# master_teststand_v1.net
KiCad netlist of a schematic drawn in EAGLE
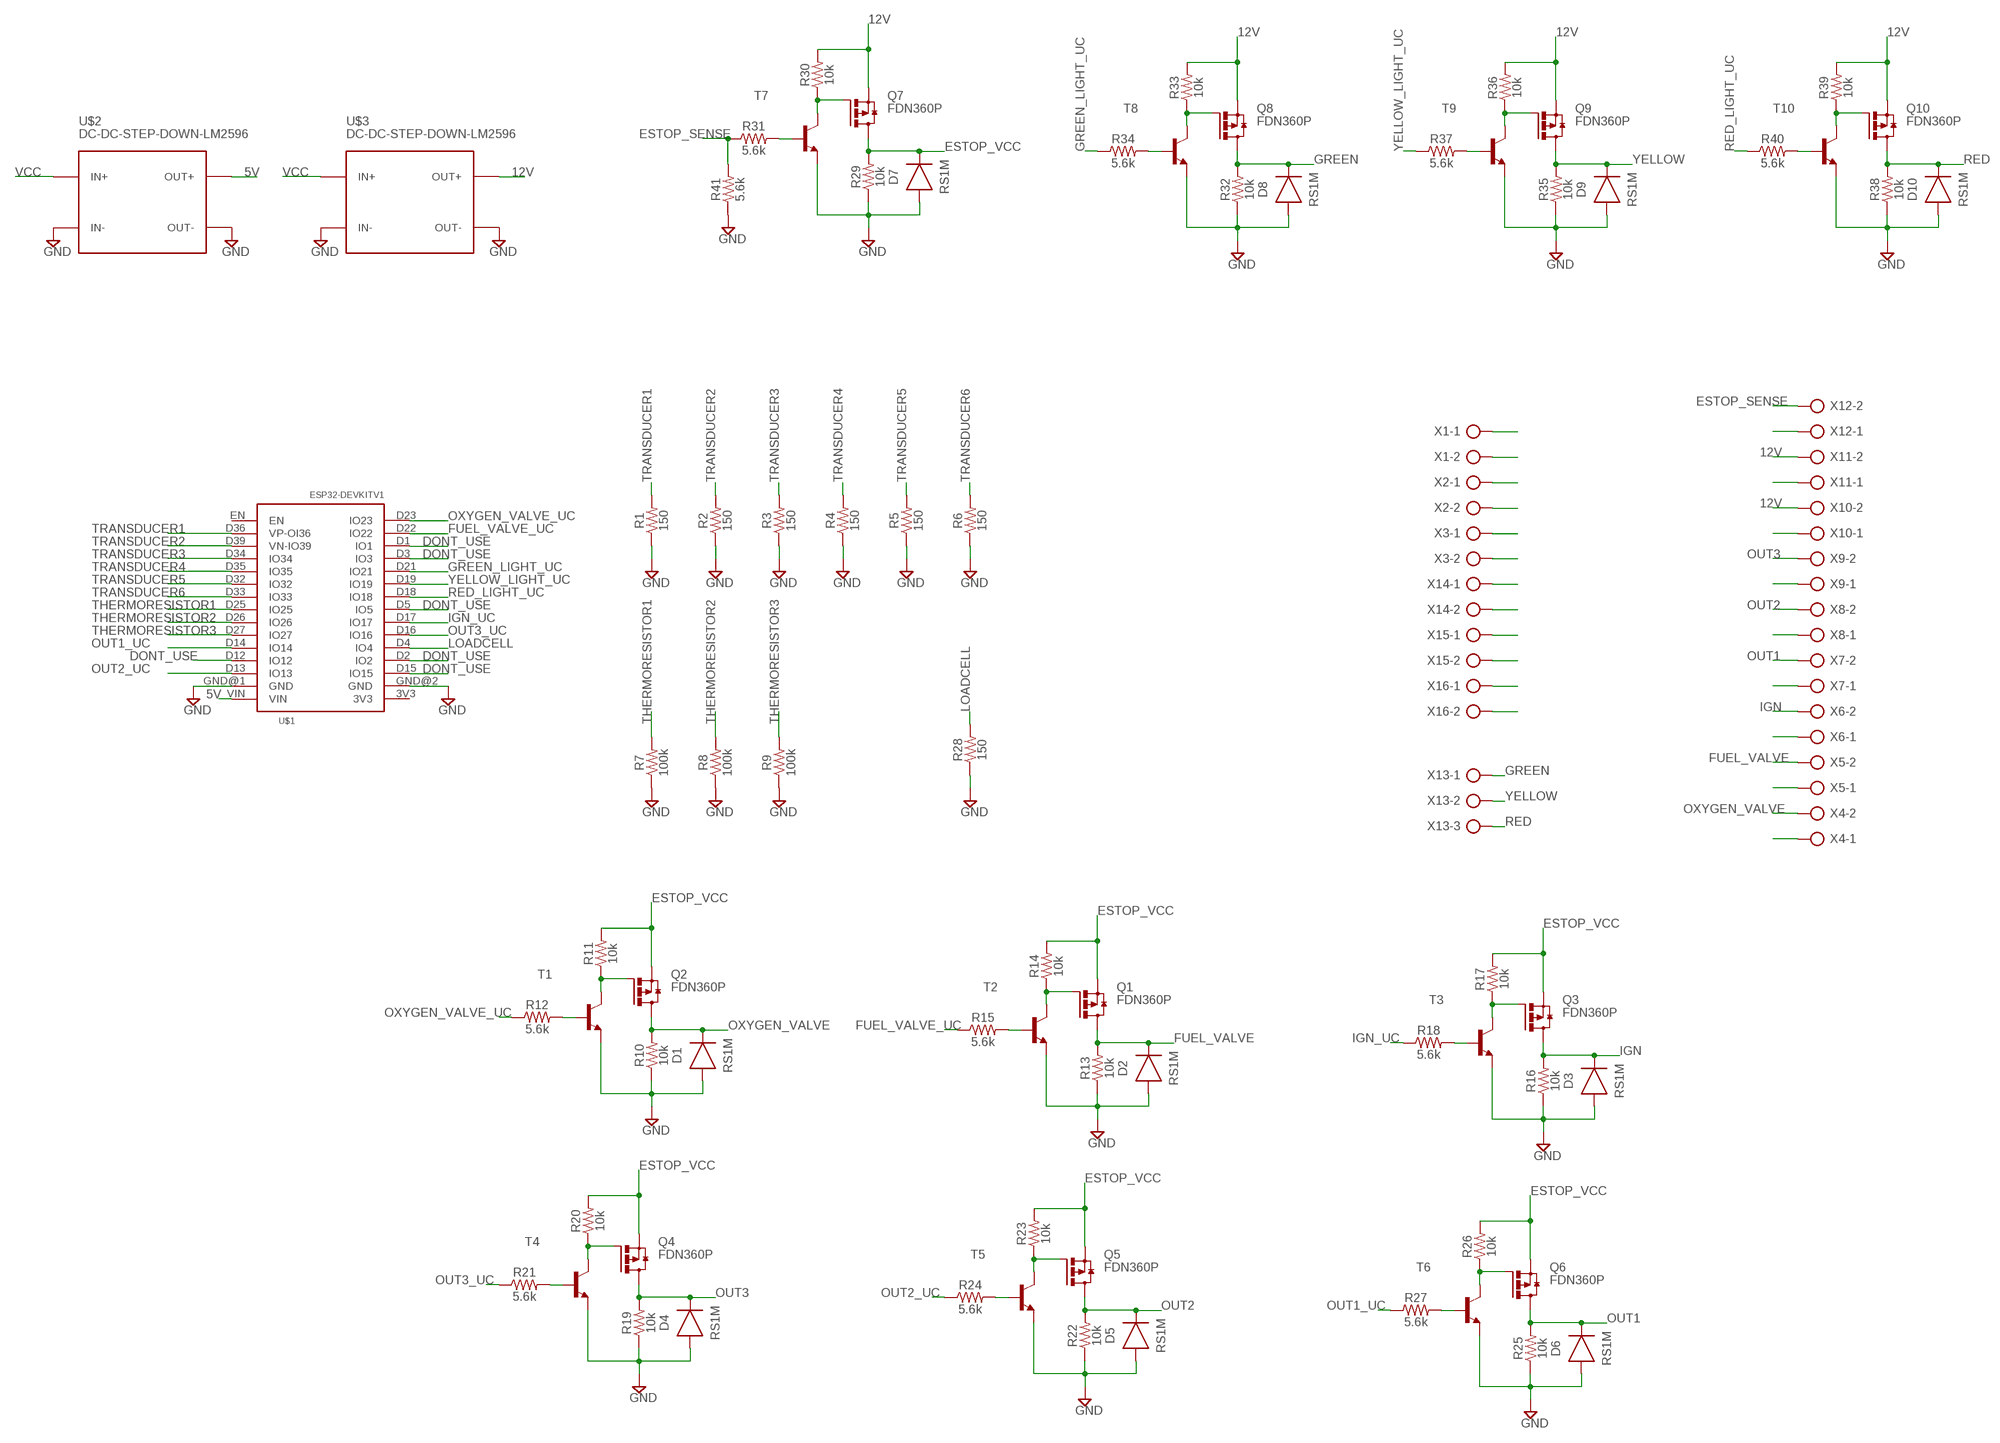
[diagram p0: schematic, sheet 1]

(export (version "E")
  (design (tool "Eeschema 10.0.6"))
  (components
    (comp (ref "D1")
      (value "RS1M")
      (footprint "eagle-import:DIOM5226X290N")
      (fields (field (name "MANUFACTURER") "ON Semiconductor "))
      (libsource (lib "eagle-import") (part "DIODE__SMARS1M"))
    )
    (comp (ref "D2")
      (value "RS1M")
      (footprint "eagle-import:DIOM5226X290N")
      (fields (field (name "MANUFACTURER") "ON Semiconductor "))
      (libsource (lib "eagle-import") (part "DIODE__SMARS1M"))
    )
    (comp (ref "D3")
      (value "RS1M")
      (footprint "eagle-import:DIOM5226X290N")
      (fields (field (name "MANUFACTURER") "ON Semiconductor "))
      (libsource (lib "eagle-import") (part "DIODE__SMARS1M"))
    )
    (comp (ref "D4")
      (value "RS1M")
      (footprint "eagle-import:DIOM5226X290N")
      (fields (field (name "MANUFACTURER") "ON Semiconductor "))
      (libsource (lib "eagle-import") (part "DIODE__SMARS1M"))
    )
    (comp (ref "D5")
      (value "RS1M")
      (footprint "eagle-import:DIOM5226X290N")
      (fields (field (name "MANUFACTURER") "ON Semiconductor "))
      (libsource (lib "eagle-import") (part "DIODE__SMARS1M"))
    )
    (comp (ref "D6")
      (value "RS1M")
      (footprint "eagle-import:DIOM5226X290N")
      (fields (field (name "MANUFACTURER") "ON Semiconductor "))
      (libsource (lib "eagle-import") (part "DIODE__SMARS1M"))
    )
    (comp (ref "D7")
      (value "RS1M")
      (footprint "eagle-import:DIOM5226X290N")
      (fields (field (name "MANUFACTURER") "ON Semiconductor "))
      (libsource (lib "eagle-import") (part "DIODE__SMARS1M"))
    )
    (comp (ref "D8")
      (value "RS1M")
      (footprint "eagle-import:DIOM5226X290N")
      (fields (field (name "MANUFACTURER") "ON Semiconductor "))
      (libsource (lib "eagle-import") (part "DIODE__SMARS1M"))
    )
    (comp (ref "D9")
      (value "RS1M")
      (footprint "eagle-import:DIOM5226X290N")
      (fields (field (name "MANUFACTURER") "ON Semiconductor "))
      (libsource (lib "eagle-import") (part "DIODE__SMARS1M"))
    )
    (comp (ref "D10")
      (value "RS1M")
      (footprint "eagle-import:DIOM5226X290N")
      (fields (field (name "MANUFACTURER") "ON Semiconductor "))
      (libsource (lib "eagle-import") (part "DIODE__SMARS1M"))
    )
    (comp (ref "Q1")
      (value "FDN360P")
      (footprint "eagle-import:SUPER-SOT3")
      (libsource (lib "eagle-import") (part "FDN360P"))
    )
    (comp (ref "Q2")
      (value "FDN360P")
      (footprint "eagle-import:SUPER-SOT3")
      (libsource (lib "eagle-import") (part "FDN360P"))
    )
    (comp (ref "Q3")
      (value "FDN360P")
      (footprint "eagle-import:SUPER-SOT3")
      (libsource (lib "eagle-import") (part "FDN360P"))
    )
    (comp (ref "Q4")
      (value "FDN360P")
      (footprint "eagle-import:SUPER-SOT3")
      (libsource (lib "eagle-import") (part "FDN360P"))
    )
    (comp (ref "Q5")
      (value "FDN360P")
      (footprint "eagle-import:SUPER-SOT3")
      (libsource (lib "eagle-import") (part "FDN360P"))
    )
    (comp (ref "Q6")
      (value "FDN360P")
      (footprint "eagle-import:SUPER-SOT3")
      (libsource (lib "eagle-import") (part "FDN360P"))
    )
    (comp (ref "Q7")
      (value "FDN360P")
      (footprint "eagle-import:SUPER-SOT3")
      (libsource (lib "eagle-import") (part "FDN360P"))
    )
    (comp (ref "Q8")
      (value "FDN360P")
      (footprint "eagle-import:SUPER-SOT3")
      (libsource (lib "eagle-import") (part "FDN360P"))
    )
    (comp (ref "Q9")
      (value "FDN360P")
      (footprint "eagle-import:SUPER-SOT3")
      (libsource (lib "eagle-import") (part "FDN360P"))
    )
    (comp (ref "Q10")
      (value "FDN360P")
      (footprint "eagle-import:SUPER-SOT3")
      (libsource (lib "eagle-import") (part "FDN360P"))
    )
    (comp (ref "R1")
      (value "150")
      (footprint "eagle-import:0603")
      (libsource (lib "eagle-import") (part "150OHM-0603-1/10W-1%"))
    )
    (comp (ref "R2")
      (value "150")
      (footprint "eagle-import:0603")
      (libsource (lib "eagle-import") (part "150OHM-0603-1/10W-1%"))
    )
    (comp (ref "R3")
      (value "150")
      (footprint "eagle-import:0603")
      (libsource (lib "eagle-import") (part "150OHM-0603-1/10W-1%"))
    )
    (comp (ref "R4")
      (value "150")
      (footprint "eagle-import:0603")
      (libsource (lib "eagle-import") (part "150OHM-0603-1/10W-1%"))
    )
    (comp (ref "R5")
      (value "150")
      (footprint "eagle-import:0603")
      (libsource (lib "eagle-import") (part "150OHM-0603-1/10W-1%"))
    )
    (comp (ref "R6")
      (value "150")
      (footprint "eagle-import:0603")
      (libsource (lib "eagle-import") (part "150OHM-0603-1/10W-1%"))
    )
    (comp (ref "R7")
      (value "100k")
      (footprint "eagle-import:0603")
      (libsource (lib "eagle-import") (part "100KOHM-0603-1/10W-1%"))
    )
    (comp (ref "R8")
      (value "100k")
      (footprint "eagle-import:0603")
      (libsource (lib "eagle-import") (part "100KOHM-0603-1/10W-1%"))
    )
    (comp (ref "R9")
      (value "100k")
      (footprint "eagle-import:0603")
      (libsource (lib "eagle-import") (part "100KOHM-0603-1/10W-1%"))
    )
    (comp (ref "R10")
      (value "10k")
      (footprint "eagle-import:0603")
      (libsource (lib "eagle-import") (part "10KOHM-0603-1/10W-1%"))
    )
    (comp (ref "R11")
      (value "10k")
      (footprint "eagle-import:0603")
      (libsource (lib "eagle-import") (part "10KOHM-0603-1/10W-1%"))
    )
    (comp (ref "R12")
      (value "5.6k")
      (footprint "eagle-import:0603")
      (libsource (lib "eagle-import") (part "5.6KOHM-0603-1/10W-1%"))
    )
    (comp (ref "R13")
      (value "10k")
      (footprint "eagle-import:0603")
      (libsource (lib "eagle-import") (part "10KOHM-0603-1/10W-1%"))
    )
    (comp (ref "R14")
      (value "10k")
      (footprint "eagle-import:0603")
      (libsource (lib "eagle-import") (part "10KOHM-0603-1/10W-1%"))
    )
    (comp (ref "R15")
      (value "5.6k")
      (footprint "eagle-import:0603")
      (libsource (lib "eagle-import") (part "5.6KOHM-0603-1/10W-1%"))
    )
    (comp (ref "R16")
      (value "10k")
      (footprint "eagle-import:0603")
      (libsource (lib "eagle-import") (part "10KOHM-0603-1/10W-1%"))
    )
    (comp (ref "R17")
      (value "10k")
      (footprint "eagle-import:0603")
      (libsource (lib "eagle-import") (part "10KOHM-0603-1/10W-1%"))
    )
    (comp (ref "R18")
      (value "5.6k")
      (footprint "eagle-import:0603")
      (libsource (lib "eagle-import") (part "5.6KOHM-0603-1/10W-1%"))
    )
    (comp (ref "R19")
      (value "10k")
      (footprint "eagle-import:0603")
      (libsource (lib "eagle-import") (part "10KOHM-0603-1/10W-1%"))
    )
    (comp (ref "R20")
      (value "10k")
      (footprint "eagle-import:0603")
      (libsource (lib "eagle-import") (part "10KOHM-0603-1/10W-1%"))
    )
    (comp (ref "R21")
      (value "5.6k")
      (footprint "eagle-import:0603")
      (libsource (lib "eagle-import") (part "5.6KOHM-0603-1/10W-1%"))
    )
    (comp (ref "R22")
      (value "10k")
      (footprint "eagle-import:0603")
      (libsource (lib "eagle-import") (part "10KOHM-0603-1/10W-1%"))
    )
    (comp (ref "R23")
      (value "10k")
      (footprint "eagle-import:0603")
      (libsource (lib "eagle-import") (part "10KOHM-0603-1/10W-1%"))
    )
    (comp (ref "R24")
      (value "5.6k")
      (footprint "eagle-import:0603")
      (libsource (lib "eagle-import") (part "5.6KOHM-0603-1/10W-1%"))
    )
    (comp (ref "R25")
      (value "10k")
      (footprint "eagle-import:0603")
      (libsource (lib "eagle-import") (part "10KOHM-0603-1/10W-1%"))
    )
    (comp (ref "R26")
      (value "10k")
      (footprint "eagle-import:0603")
      (libsource (lib "eagle-import") (part "10KOHM-0603-1/10W-1%"))
    )
    (comp (ref "R27")
      (value "5.6k")
      (footprint "eagle-import:0603")
      (libsource (lib "eagle-import") (part "5.6KOHM-0603-1/10W-1%"))
    )
    (comp (ref "R28")
      (value "150")
      (footprint "eagle-import:0603")
      (libsource (lib "eagle-import") (part "150OHM-0603-1/10W-1%"))
    )
    (comp (ref "R29")
      (value "10k")
      (footprint "eagle-import:0603")
      (libsource (lib "eagle-import") (part "10KOHM-0603-1/10W-1%"))
    )
    (comp (ref "R30")
      (value "10k")
      (footprint "eagle-import:0603")
      (libsource (lib "eagle-import") (part "10KOHM-0603-1/10W-1%"))
    )
    (comp (ref "R31")
      (value "5.6k")
      (footprint "eagle-import:0603")
      (libsource (lib "eagle-import") (part "5.6KOHM-0603-1/10W-1%"))
    )
    (comp (ref "R32")
      (value "10k")
      (footprint "eagle-import:0603")
      (libsource (lib "eagle-import") (part "10KOHM-0603-1/10W-1%"))
    )
    (comp (ref "R33")
      (value "10k")
      (footprint "eagle-import:0603")
      (libsource (lib "eagle-import") (part "10KOHM-0603-1/10W-1%"))
    )
    (comp (ref "R34")
      (value "5.6k")
      (footprint "eagle-import:0603")
      (libsource (lib "eagle-import") (part "5.6KOHM-0603-1/10W-1%"))
    )
    (comp (ref "R35")
      (value "10k")
      (footprint "eagle-import:0603")
      (libsource (lib "eagle-import") (part "10KOHM-0603-1/10W-1%"))
    )
    (comp (ref "R36")
      (value "10k")
      (footprint "eagle-import:0603")
      (libsource (lib "eagle-import") (part "10KOHM-0603-1/10W-1%"))
    )
    (comp (ref "R37")
      (value "5.6k")
      (footprint "eagle-import:0603")
      (libsource (lib "eagle-import") (part "5.6KOHM-0603-1/10W-1%"))
    )
    (comp (ref "R38")
      (value "10k")
      (footprint "eagle-import:0603")
      (libsource (lib "eagle-import") (part "10KOHM-0603-1/10W-1%"))
    )
    (comp (ref "R39")
      (value "10k")
      (footprint "eagle-import:0603")
      (libsource (lib "eagle-import") (part "10KOHM-0603-1/10W-1%"))
    )
    (comp (ref "R40")
      (value "5.6k")
      (footprint "eagle-import:0603")
      (libsource (lib "eagle-import") (part "5.6KOHM-0603-1/10W-1%"))
    )
    (comp (ref "R41")
      (value "5.6k")
      (footprint "eagle-import:0603")
      (libsource (lib "eagle-import") (part "5.6KOHM-0603-1/10W-1%"))
    )
    (comp (ref "T1")
      (value "MMBT2222ALT1-NPN-SOT23-BEC")
      (footprint "eagle-import:SOT23-BEC")
      (libsource (lib "eagle-import") (part "-NPN-SOT23-BECMMBT2222ALT1"))
    )
    (comp (ref "T2")
      (value "MMBT2222ALT1-NPN-SOT23-BEC")
      (footprint "eagle-import:SOT23-BEC")
      (libsource (lib "eagle-import") (part "-NPN-SOT23-BECMMBT2222ALT1"))
    )
    (comp (ref "T3")
      (value "MMBT2222ALT1-NPN-SOT23-BEC")
      (footprint "eagle-import:SOT23-BEC")
      (libsource (lib "eagle-import") (part "-NPN-SOT23-BECMMBT2222ALT1"))
    )
    (comp (ref "T4")
      (value "MMBT2222ALT1-NPN-SOT23-BEC")
      (footprint "eagle-import:SOT23-BEC")
      (libsource (lib "eagle-import") (part "-NPN-SOT23-BECMMBT2222ALT1"))
    )
    (comp (ref "T5")
      (value "MMBT2222ALT1-NPN-SOT23-BEC")
      (footprint "eagle-import:SOT23-BEC")
      (libsource (lib "eagle-import") (part "-NPN-SOT23-BECMMBT2222ALT1"))
    )
    (comp (ref "T6")
      (value "MMBT2222ALT1-NPN-SOT23-BEC")
      (footprint "eagle-import:SOT23-BEC")
      (libsource (lib "eagle-import") (part "-NPN-SOT23-BECMMBT2222ALT1"))
    )
    (comp (ref "T7")
      (value "MMBT2222ALT1-NPN-SOT23-BEC")
      (footprint "eagle-import:SOT23-BEC")
      (libsource (lib "eagle-import") (part "-NPN-SOT23-BECMMBT2222ALT1"))
    )
    (comp (ref "T8")
      (value "MMBT2222ALT1-NPN-SOT23-BEC")
      (footprint "eagle-import:SOT23-BEC")
      (libsource (lib "eagle-import") (part "-NPN-SOT23-BECMMBT2222ALT1"))
    )
    (comp (ref "T9")
      (value "MMBT2222ALT1-NPN-SOT23-BEC")
      (footprint "eagle-import:SOT23-BEC")
      (libsource (lib "eagle-import") (part "-NPN-SOT23-BECMMBT2222ALT1"))
    )
    (comp (ref "T10")
      (value "MMBT2222ALT1-NPN-SOT23-BEC")
      (footprint "eagle-import:SOT23-BEC")
      (libsource (lib "eagle-import") (part "-NPN-SOT23-BECMMBT2222ALT1"))
    )
    (comp (ref "U$1")
      (value "ESP32DEVKITV1")
      (footprint "eagle-import:ESP32-DEVKITV1")
      (libsource (lib "eagle-import") (part "ESP32DEVKITV1"))
    )
    (comp (ref "U$2")
      (value "DC-DC-STEP-DOWN-LM2596")
      (footprint "eagle-import:DC-DC-STEP-DOWN-LM2596")
      (libsource (lib "eagle-import") (part "DC-DC-STEP-DOWN-LM2596"))
    )
    (comp (ref "U$3")
      (value "DC-DC-STEP-DOWN-LM2596")
      (footprint "eagle-import:DC-DC-STEP-DOWN-LM2596")
      (libsource (lib "eagle-import") (part "DC-DC-STEP-DOWN-LM2596"))
    )
    (comp (ref "X1")
      (value "AK300/2")
      (footprint "eagle-import:AK300_2")
      (libsource (lib "eagle-import") (part "AK300/2"))
    )
    (comp (ref "X2")
      (value "AK300/2")
      (footprint "eagle-import:AK300_2")
      (libsource (lib "eagle-import") (part "AK300/2"))
    )
    (comp (ref "X3")
      (value "AK300/2")
      (footprint "eagle-import:AK300_2")
      (libsource (lib "eagle-import") (part "AK300/2"))
    )
    (comp (ref "X4")
      (value "AK300/2")
      (footprint "eagle-import:AK300_2")
      (libsource (lib "eagle-import") (part "AK300/2"))
    )
    (comp (ref "X5")
      (value "AK300/2")
      (footprint "eagle-import:AK300_2")
      (libsource (lib "eagle-import") (part "AK300/2"))
    )
    (comp (ref "X6")
      (value "AK300/2")
      (footprint "eagle-import:AK300_2")
      (libsource (lib "eagle-import") (part "AK300/2"))
    )
    (comp (ref "X7")
      (value "AK300/2")
      (footprint "eagle-import:AK300_2")
      (libsource (lib "eagle-import") (part "AK300/2"))
    )
    (comp (ref "X8")
      (value "AK300/2")
      (footprint "eagle-import:AK300_2")
      (libsource (lib "eagle-import") (part "AK300/2"))
    )
    (comp (ref "X9")
      (value "AK300/2")
      (footprint "eagle-import:AK300_2")
      (libsource (lib "eagle-import") (part "AK300/2"))
    )
    (comp (ref "X10")
      (value "AK300/2")
      (footprint "eagle-import:AK300_2")
      (libsource (lib "eagle-import") (part "AK300/2"))
    )
    (comp (ref "X11")
      (value "AK300/2")
      (footprint "eagle-import:AK300_2")
      (libsource (lib "eagle-import") (part "AK300/2"))
    )
    (comp (ref "X12")
      (value "AK300/2")
      (footprint "eagle-import:AK300_2")
      (libsource (lib "eagle-import") (part "AK300/2"))
    )
    (comp (ref "X13")
      (value "AK300/3")
      (footprint "eagle-import:AK300_3")
      (libsource (lib "eagle-import") (part "AK300/3"))
    )
    (comp (ref "X14")
      (value "AK300/2")
      (footprint "eagle-import:AK300_2")
      (libsource (lib "eagle-import") (part "AK300/2"))
    )
    (comp (ref "X15")
      (value "AK300/2")
      (footprint "eagle-import:AK300_2")
      (libsource (lib "eagle-import") (part "AK300/2"))
    )
    (comp (ref "X16")
      (value "AK300/2")
      (footprint "eagle-import:AK300_2")
      (libsource (lib "eagle-import") (part "AK300/2"))
    )
  )
  (nets
    (net (code "1") (name "/5V") (class "Default")
      (node (ref "U$1") (pin "VIN") (pinfunction "VIN_VIN") (pintype "bidirectional"))
      (node (ref "U$2") (pin "OUT+") (pinfunction "OUT+_OUT+") (pintype "bidirectional"))
    )
    (net (code "2") (name "/12V") (class "Default")
      (node (ref "Q10") (pin "2") (pinfunction "S_2") (pintype "passive"))
      (node (ref "Q7") (pin "2") (pinfunction "S_2") (pintype "passive"))
      (node (ref "Q8") (pin "2") (pinfunction "S_2") (pintype "passive"))
      (node (ref "Q9") (pin "2") (pinfunction "S_2") (pintype "passive"))
      (node (ref "R30") (pin "2") (pinfunction "2_2") (pintype "passive"))
      (node (ref "R33") (pin "2") (pinfunction "2_2") (pintype "passive"))
      (node (ref "R36") (pin "2") (pinfunction "2_2") (pintype "passive"))
      (node (ref "R39") (pin "2") (pinfunction "2_2") (pintype "passive"))
      (node (ref "U$3") (pin "OUT+") (pinfunction "OUT+_OUT+") (pintype "bidirectional"))
      (node (ref "X10") (pin "2") (pinfunction "KL_2") (pintype "passive"))
      (node (ref "X11") (pin "2") (pinfunction "KL_2") (pintype "passive"))
    )
    (net (code "3") (name "/DONT_USE") (class "Default")
      (node (ref "U$1") (pin "D1") (pinfunction "IO1_D1") (pintype "bidirectional"))
      (node (ref "U$1") (pin "D12") (pinfunction "IO12_D12") (pintype "bidirectional"))
      (node (ref "U$1") (pin "D15") (pinfunction "IO15_D15") (pintype "bidirectional"))
      (node (ref "U$1") (pin "D2") (pinfunction "IO2_D2") (pintype "bidirectional"))
      (node (ref "U$1") (pin "D3") (pinfunction "IO3_D3") (pintype "bidirectional"))
      (node (ref "U$1") (pin "D5") (pinfunction "IO5_D5") (pintype "bidirectional"))
    )
    (net (code "4") (name "/ESTOP_SENSE") (class "Default")
      (node (ref "R31") (pin "1") (pinfunction "1_1") (pintype "passive"))
      (node (ref "R41") (pin "2") (pinfunction "2_2") (pintype "passive"))
      (node (ref "X12") (pin "2") (pinfunction "KL_2") (pintype "passive"))
    )
    (net (code "5") (name "/ESTOP_VCC") (class "Default")
      (node (ref "D7") (pin "1") (pinfunction "C_1") (pintype "passive"))
      (node (ref "Q1") (pin "2") (pinfunction "S_2") (pintype "passive"))
      (node (ref "Q2") (pin "2") (pinfunction "S_2") (pintype "passive"))
      (node (ref "Q3") (pin "2") (pinfunction "S_2") (pintype "passive"))
      (node (ref "Q4") (pin "2") (pinfunction "S_2") (pintype "passive"))
      (node (ref "Q5") (pin "2") (pinfunction "S_2") (pintype "passive"))
      (node (ref "Q6") (pin "2") (pinfunction "S_2") (pintype "passive"))
      (node (ref "Q7") (pin "3") (pinfunction "D_3") (pintype "passive"))
      (node (ref "R11") (pin "2") (pinfunction "2_2") (pintype "passive"))
      (node (ref "R14") (pin "2") (pinfunction "2_2") (pintype "passive"))
      (node (ref "R17") (pin "2") (pinfunction "2_2") (pintype "passive"))
      (node (ref "R20") (pin "2") (pinfunction "2_2") (pintype "passive"))
      (node (ref "R23") (pin "2") (pinfunction "2_2") (pintype "passive"))
      (node (ref "R26") (pin "2") (pinfunction "2_2") (pintype "passive"))
      (node (ref "R29") (pin "2") (pinfunction "2_2") (pintype "passive"))
    )
    (net (code "6") (name "/FUEL_VALVE") (class "Default")
      (node (ref "D2") (pin "1") (pinfunction "C_1") (pintype "passive"))
      (node (ref "Q1") (pin "3") (pinfunction "D_3") (pintype "passive"))
      (node (ref "R13") (pin "2") (pinfunction "2_2") (pintype "passive"))
      (node (ref "X5") (pin "2") (pinfunction "KL_2") (pintype "passive"))
    )
    (net (code "7") (name "/FUEL_VALVE_UC") (class "Default")
      (node (ref "R15") (pin "1") (pinfunction "1_1") (pintype "passive"))
      (node (ref "U$1") (pin "D22") (pinfunction "IO22_D22") (pintype "bidirectional"))
    )
    (net (code "8") (name "/GREEN") (class "Default")
      (node (ref "D8") (pin "1") (pinfunction "C_1") (pintype "passive"))
      (node (ref "Q8") (pin "3") (pinfunction "D_3") (pintype "passive"))
      (node (ref "R32") (pin "2") (pinfunction "2_2") (pintype "passive"))
      (node (ref "X13") (pin "1") (pinfunction "KL_1") (pintype "passive"))
    )
    (net (code "9") (name "/GREEN_LIGHT_UC") (class "Default")
      (node (ref "R34") (pin "1") (pinfunction "1_1") (pintype "passive"))
      (node (ref "U$1") (pin "D21") (pinfunction "IO21_D21") (pintype "bidirectional"))
    )
    (net (code "10") (name "/IGN") (class "Default")
      (node (ref "D3") (pin "1") (pinfunction "C_1") (pintype "passive"))
      (node (ref "Q3") (pin "3") (pinfunction "D_3") (pintype "passive"))
      (node (ref "R16") (pin "2") (pinfunction "2_2") (pintype "passive"))
      (node (ref "X6") (pin "2") (pinfunction "KL_2") (pintype "passive"))
    )
    (net (code "11") (name "/IGN_UC") (class "Default")
      (node (ref "R18") (pin "1") (pinfunction "1_1") (pintype "passive"))
      (node (ref "U$1") (pin "D17") (pinfunction "IO17_D17") (pintype "bidirectional"))
    )
    (net (code "12") (name "/LOADCELL") (class "Default")
      (node (ref "R28") (pin "2") (pinfunction "2_2") (pintype "passive"))
      (node (ref "U$1") (pin "D4") (pinfunction "IO4_D4") (pintype "bidirectional"))
    )
    (net (code "13") (name "/OUT1") (class "Default")
      (node (ref "D6") (pin "1") (pinfunction "C_1") (pintype "passive"))
      (node (ref "Q6") (pin "3") (pinfunction "D_3") (pintype "passive"))
      (node (ref "R25") (pin "2") (pinfunction "2_2") (pintype "passive"))
      (node (ref "X7") (pin "2") (pinfunction "KL_2") (pintype "passive"))
    )
    (net (code "14") (name "/OUT1_UC") (class "Default")
      (node (ref "R27") (pin "1") (pinfunction "1_1") (pintype "passive"))
      (node (ref "U$1") (pin "D14") (pinfunction "IO14_D14") (pintype "bidirectional"))
    )
    (net (code "15") (name "/OUT2") (class "Default")
      (node (ref "D5") (pin "1") (pinfunction "C_1") (pintype "passive"))
      (node (ref "Q5") (pin "3") (pinfunction "D_3") (pintype "passive"))
      (node (ref "R22") (pin "2") (pinfunction "2_2") (pintype "passive"))
      (node (ref "X8") (pin "1") (pinfunction "KL_1") (pintype "passive"))
      (node (ref "X8") (pin "2") (pinfunction "KL_2") (pintype "passive"))
    )
    (net (code "16") (name "/OUT2_UC") (class "Default")
      (node (ref "R24") (pin "1") (pinfunction "1_1") (pintype "passive"))
      (node (ref "U$1") (pin "D13") (pinfunction "IO13_D13") (pintype "bidirectional"))
    )
    (net (code "17") (name "/OUT3") (class "Default")
      (node (ref "D4") (pin "1") (pinfunction "C_1") (pintype "passive"))
      (node (ref "Q4") (pin "3") (pinfunction "D_3") (pintype "passive"))
      (node (ref "R19") (pin "2") (pinfunction "2_2") (pintype "passive"))
      (node (ref "X9") (pin "2") (pinfunction "KL_2") (pintype "passive"))
    )
    (net (code "18") (name "/OUT3_UC") (class "Default")
      (node (ref "R21") (pin "1") (pinfunction "1_1") (pintype "passive"))
      (node (ref "U$1") (pin "D16") (pinfunction "IO16_D16") (pintype "bidirectional"))
    )
    (net (code "19") (name "/OXYGEN_VALVE") (class "Default")
      (node (ref "D1") (pin "1") (pinfunction "C_1") (pintype "passive"))
      (node (ref "Q2") (pin "3") (pinfunction "D_3") (pintype "passive"))
      (node (ref "R10") (pin "2") (pinfunction "2_2") (pintype "passive"))
      (node (ref "X4") (pin "2") (pinfunction "KL_2") (pintype "passive"))
    )
    (net (code "20") (name "/OXYGEN_VALVE_UC") (class "Default")
      (node (ref "R12") (pin "1") (pinfunction "1_1") (pintype "passive"))
      (node (ref "U$1") (pin "D23") (pinfunction "IO23_D23") (pintype "bidirectional"))
    )
    (net (code "21") (name "/RED") (class "Default")
      (node (ref "D10") (pin "1") (pinfunction "C_1") (pintype "passive"))
      (node (ref "Q10") (pin "3") (pinfunction "D_3") (pintype "passive"))
      (node (ref "R38") (pin "2") (pinfunction "2_2") (pintype "passive"))
      (node (ref "X13") (pin "3") (pinfunction "KL_3") (pintype "passive"))
    )
    (net (code "22") (name "/RED_LIGHT_UC") (class "Default")
      (node (ref "R40") (pin "1") (pinfunction "1_1") (pintype "passive"))
      (node (ref "U$1") (pin "D18") (pinfunction "IO18_D18") (pintype "bidirectional"))
    )
    (net (code "23") (name "/THERMORESISTOR1") (class "Default")
      (node (ref "R7") (pin "2") (pinfunction "2_2") (pintype "passive"))
      (node (ref "U$1") (pin "D25") (pinfunction "IO25_D25") (pintype "bidirectional"))
    )
    (net (code "24") (name "/THERMORESISTOR2") (class "Default")
      (node (ref "R8") (pin "2") (pinfunction "2_2") (pintype "passive"))
      (node (ref "U$1") (pin "D26") (pinfunction "IO26_D26") (pintype "bidirectional"))
    )
    (net (code "25") (name "/THERMORESISTOR3") (class "Default")
      (node (ref "R9") (pin "2") (pinfunction "2_2") (pintype "passive"))
      (node (ref "U$1") (pin "D27") (pinfunction "IO27_D27") (pintype "bidirectional"))
    )
    (net (code "26") (name "/TRANSDUCER1") (class "Default")
      (node (ref "R1") (pin "2") (pinfunction "2_2") (pintype "passive"))
      (node (ref "U$1") (pin "D36") (pinfunction "VP-OI36_D36") (pintype "bidirectional"))
    )
    (net (code "27") (name "/TRANSDUCER2") (class "Default")
      (node (ref "R2") (pin "2") (pinfunction "2_2") (pintype "passive"))
      (node (ref "U$1") (pin "D39") (pinfunction "VN-IO39_D39") (pintype "bidirectional"))
    )
    (net (code "28") (name "/TRANSDUCER3") (class "Default")
      (node (ref "R3") (pin "2") (pinfunction "2_2") (pintype "passive"))
      (node (ref "U$1") (pin "D34") (pinfunction "IO34_D34") (pintype "bidirectional"))
    )
    (net (code "29") (name "/TRANSDUCER4") (class "Default")
      (node (ref "R4") (pin "2") (pinfunction "2_2") (pintype "passive"))
      (node (ref "U$1") (pin "D35") (pinfunction "IO35_D35") (pintype "bidirectional"))
    )
    (net (code "30") (name "/TRANSDUCER5") (class "Default")
      (node (ref "R5") (pin "2") (pinfunction "2_2") (pintype "passive"))
      (node (ref "U$1") (pin "D32") (pinfunction "IO32_D32") (pintype "bidirectional"))
    )
    (net (code "31") (name "/TRANSDUCER6") (class "Default")
      (node (ref "R6") (pin "2") (pinfunction "2_2") (pintype "passive"))
      (node (ref "U$1") (pin "D33") (pinfunction "IO33_D33") (pintype "bidirectional"))
    )
    (net (code "32") (name "/VCC") (class "Default")
      (node (ref "U$2") (pin "IN+") (pinfunction "IN+_IN+") (pintype "bidirectional"))
      (node (ref "U$3") (pin "IN+") (pinfunction "IN+_IN+") (pintype "bidirectional"))
    )
    (net (code "33") (name "/YELLOW") (class "Default")
      (node (ref "D9") (pin "1") (pinfunction "C_1") (pintype "passive"))
      (node (ref "Q9") (pin "3") (pinfunction "D_3") (pintype "passive"))
      (node (ref "R35") (pin "2") (pinfunction "2_2") (pintype "passive"))
      (node (ref "X13") (pin "2") (pinfunction "KL_2") (pintype "passive"))
    )
    (net (code "34") (name "/YELLOW_LIGHT_UC") (class "Default")
      (node (ref "R37") (pin "1") (pinfunction "1_1") (pintype "passive"))
      (node (ref "U$1") (pin "D19") (pinfunction "IO19_D19") (pintype "bidirectional"))
    )
    (net (code "35") (name "GND") (class "Default")
      (node (ref "D1") (pin "2") (pinfunction "A_2") (pintype "passive"))
      (node (ref "D10") (pin "2") (pinfunction "A_2") (pintype "passive"))
      (node (ref "D2") (pin "2") (pinfunction "A_2") (pintype "passive"))
      (node (ref "D3") (pin "2") (pinfunction "A_2") (pintype "passive"))
      (node (ref "D4") (pin "2") (pinfunction "A_2") (pintype "passive"))
      (node (ref "D5") (pin "2") (pinfunction "A_2") (pintype "passive"))
      (node (ref "D6") (pin "2") (pinfunction "A_2") (pintype "passive"))
      (node (ref "D7") (pin "2") (pinfunction "A_2") (pintype "passive"))
      (node (ref "D8") (pin "2") (pinfunction "A_2") (pintype "passive"))
      (node (ref "D9") (pin "2") (pinfunction "A_2") (pintype "passive"))
      (node (ref "R1") (pin "1") (pinfunction "1_1") (pintype "passive"))
      (node (ref "R10") (pin "1") (pinfunction "1_1") (pintype "passive"))
      (node (ref "R13") (pin "1") (pinfunction "1_1") (pintype "passive"))
      (node (ref "R16") (pin "1") (pinfunction "1_1") (pintype "passive"))
      (node (ref "R19") (pin "1") (pinfunction "1_1") (pintype "passive"))
      (node (ref "R2") (pin "1") (pinfunction "1_1") (pintype "passive"))
      (node (ref "R22") (pin "1") (pinfunction "1_1") (pintype "passive"))
      (node (ref "R25") (pin "1") (pinfunction "1_1") (pintype "passive"))
      (node (ref "R28") (pin "1") (pinfunction "1_1") (pintype "passive"))
      (node (ref "R29") (pin "1") (pinfunction "1_1") (pintype "passive"))
      (node (ref "R3") (pin "1") (pinfunction "1_1") (pintype "passive"))
      (node (ref "R32") (pin "1") (pinfunction "1_1") (pintype "passive"))
      (node (ref "R35") (pin "1") (pinfunction "1_1") (pintype "passive"))
      (node (ref "R38") (pin "1") (pinfunction "1_1") (pintype "passive"))
      (node (ref "R4") (pin "1") (pinfunction "1_1") (pintype "passive"))
      (node (ref "R41") (pin "1") (pinfunction "1_1") (pintype "passive"))
      (node (ref "R5") (pin "1") (pinfunction "1_1") (pintype "passive"))
      (node (ref "R6") (pin "1") (pinfunction "1_1") (pintype "passive"))
      (node (ref "R7") (pin "1") (pinfunction "1_1") (pintype "passive"))
      (node (ref "R8") (pin "1") (pinfunction "1_1") (pintype "passive"))
      (node (ref "R9") (pin "1") (pinfunction "1_1") (pintype "passive"))
      (node (ref "T1") (pin "E") (pinfunction "E_E") (pintype "passive"))
      (node (ref "T10") (pin "E") (pinfunction "E_E") (pintype "passive"))
      (node (ref "T2") (pin "E") (pinfunction "E_E") (pintype "passive"))
      (node (ref "T3") (pin "E") (pinfunction "E_E") (pintype "passive"))
      (node (ref "T4") (pin "E") (pinfunction "E_E") (pintype "passive"))
      (node (ref "T5") (pin "E") (pinfunction "E_E") (pintype "passive"))
      (node (ref "T6") (pin "E") (pinfunction "E_E") (pintype "passive"))
      (node (ref "T7") (pin "E") (pinfunction "E_E") (pintype "passive"))
      (node (ref "T8") (pin "E") (pinfunction "E_E") (pintype "passive"))
      (node (ref "T9") (pin "E") (pinfunction "E_E") (pintype "passive"))
      (node (ref "U$1") (pin "GND@1") (pinfunction "GND_GND@1") (pintype "bidirectional"))
      (node (ref "U$1") (pin "GND@2") (pinfunction "GND_GND@2") (pintype "bidirectional"))
      (node (ref "U$2") (pin "IN-") (pinfunction "IN-_IN-") (pintype "bidirectional"))
      (node (ref "U$2") (pin "OUT-") (pinfunction "OUT-_OUT-") (pintype "bidirectional"))
      (node (ref "U$3") (pin "IN-") (pinfunction "IN-_IN-") (pintype "bidirectional"))
      (node (ref "U$3") (pin "OUT-") (pinfunction "OUT-_OUT-") (pintype "bidirectional"))
    )
    (net (code "36") (name "Net-(Q1-G)") (class "Default")
      (node (ref "Q1") (pin "1") (pinfunction "G_1") (pintype "passive"))
      (node (ref "R14") (pin "1") (pinfunction "1_1") (pintype "passive"))
      (node (ref "T2") (pin "C") (pinfunction "C_C") (pintype "passive"))
    )
    (net (code "37") (name "Net-(Q2-G)") (class "Default")
      (node (ref "Q2") (pin "1") (pinfunction "G_1") (pintype "passive"))
      (node (ref "R11") (pin "1") (pinfunction "1_1") (pintype "passive"))
      (node (ref "T1") (pin "C") (pinfunction "C_C") (pintype "passive"))
    )
    (net (code "38") (name "Net-(Q3-G)") (class "Default")
      (node (ref "Q3") (pin "1") (pinfunction "G_1") (pintype "passive"))
      (node (ref "R17") (pin "1") (pinfunction "1_1") (pintype "passive"))
      (node (ref "T3") (pin "C") (pinfunction "C_C") (pintype "passive"))
    )
    (net (code "39") (name "Net-(Q4-G)") (class "Default")
      (node (ref "Q4") (pin "1") (pinfunction "G_1") (pintype "passive"))
      (node (ref "R20") (pin "1") (pinfunction "1_1") (pintype "passive"))
      (node (ref "T4") (pin "C") (pinfunction "C_C") (pintype "passive"))
    )
    (net (code "40") (name "Net-(Q5-G)") (class "Default")
      (node (ref "Q5") (pin "1") (pinfunction "G_1") (pintype "passive"))
      (node (ref "R23") (pin "1") (pinfunction "1_1") (pintype "passive"))
      (node (ref "T5") (pin "C") (pinfunction "C_C") (pintype "passive"))
    )
    (net (code "41") (name "Net-(Q6-G)") (class "Default")
      (node (ref "Q6") (pin "1") (pinfunction "G_1") (pintype "passive"))
      (node (ref "R26") (pin "1") (pinfunction "1_1") (pintype "passive"))
      (node (ref "T6") (pin "C") (pinfunction "C_C") (pintype "passive"))
    )
    (net (code "42") (name "Net-(Q7-G)") (class "Default")
      (node (ref "Q7") (pin "1") (pinfunction "G_1") (pintype "passive"))
      (node (ref "R30") (pin "1") (pinfunction "1_1") (pintype "passive"))
      (node (ref "T7") (pin "C") (pinfunction "C_C") (pintype "passive"))
    )
    (net (code "43") (name "Net-(Q8-G)") (class "Default")
      (node (ref "Q8") (pin "1") (pinfunction "G_1") (pintype "passive"))
      (node (ref "R33") (pin "1") (pinfunction "1_1") (pintype "passive"))
      (node (ref "T8") (pin "C") (pinfunction "C_C") (pintype "passive"))
    )
    (net (code "44") (name "Net-(Q9-G)") (class "Default")
      (node (ref "Q9") (pin "1") (pinfunction "G_1") (pintype "passive"))
      (node (ref "R36") (pin "1") (pinfunction "1_1") (pintype "passive"))
      (node (ref "T9") (pin "C") (pinfunction "C_C") (pintype "passive"))
    )
    (net (code "45") (name "Net-(Q10-G)") (class "Default")
      (node (ref "Q10") (pin "1") (pinfunction "G_1") (pintype "passive"))
      (node (ref "R39") (pin "1") (pinfunction "1_1") (pintype "passive"))
      (node (ref "T10") (pin "C") (pinfunction "C_C") (pintype "passive"))
    )
    (net (code "46") (name "Net-(R12-Pad2)") (class "Default")
      (node (ref "R12") (pin "2") (pinfunction "2_2") (pintype "passive"))
      (node (ref "T1") (pin "B") (pinfunction "B_B") (pintype "passive"))
    )
    (net (code "47") (name "Net-(R15-Pad2)") (class "Default")
      (node (ref "R15") (pin "2") (pinfunction "2_2") (pintype "passive"))
      (node (ref "T2") (pin "B") (pinfunction "B_B") (pintype "passive"))
    )
    (net (code "48") (name "Net-(R18-Pad2)") (class "Default")
      (node (ref "R18") (pin "2") (pinfunction "2_2") (pintype "passive"))
      (node (ref "T3") (pin "B") (pinfunction "B_B") (pintype "passive"))
    )
    (net (code "49") (name "Net-(R21-Pad2)") (class "Default")
      (node (ref "R21") (pin "2") (pinfunction "2_2") (pintype "passive"))
      (node (ref "T4") (pin "B") (pinfunction "B_B") (pintype "passive"))
    )
    (net (code "50") (name "Net-(R24-Pad2)") (class "Default")
      (node (ref "R24") (pin "2") (pinfunction "2_2") (pintype "passive"))
      (node (ref "T5") (pin "B") (pinfunction "B_B") (pintype "passive"))
    )
    (net (code "51") (name "Net-(R27-Pad2)") (class "Default")
      (node (ref "R27") (pin "2") (pinfunction "2_2") (pintype "passive"))
      (node (ref "T6") (pin "B") (pinfunction "B_B") (pintype "passive"))
    )
    (net (code "52") (name "Net-(R31-Pad2)") (class "Default")
      (node (ref "R31") (pin "2") (pinfunction "2_2") (pintype "passive"))
      (node (ref "T7") (pin "B") (pinfunction "B_B") (pintype "passive"))
    )
    (net (code "53") (name "Net-(R34-Pad2)") (class "Default")
      (node (ref "R34") (pin "2") (pinfunction "2_2") (pintype "passive"))
      (node (ref "T8") (pin "B") (pinfunction "B_B") (pintype "passive"))
    )
    (net (code "54") (name "Net-(R37-Pad2)") (class "Default")
      (node (ref "R37") (pin "2") (pinfunction "2_2") (pintype "passive"))
      (node (ref "T9") (pin "B") (pinfunction "B_B") (pintype "passive"))
    )
    (net (code "55") (name "Net-(R40-Pad2)") (class "Default")
      (node (ref "R40") (pin "2") (pinfunction "2_2") (pintype "passive"))
      (node (ref "T10") (pin "B") (pinfunction "B_B") (pintype "passive"))
    )
    (net (code "56") (name "unconnected-(U$1-Pad3V3)") (class "Default")
      (node (ref "U$1") (pin "3V3") (pinfunction "3V3_3V3") (pintype "bidirectional"))
    )
    (net (code "57") (name "unconnected-(U$1-PadEN)") (class "Default")
      (node (ref "U$1") (pin "EN") (pinfunction "EN_EN") (pintype "bidirectional"))
    )
    (net (code "58") (name "unconnected-(X1A-KL-Pad1)") (class "Default")
      (node (ref "X1") (pin "1") (pinfunction "KL_1") (pintype "passive"))
    )
    (net (code "59") (name "unconnected-(X1B-KL-Pad2)") (class "Default")
      (node (ref "X1") (pin "2") (pinfunction "KL_2") (pintype "passive"))
    )
    (net (code "60") (name "unconnected-(X2A-KL-Pad1)") (class "Default")
      (node (ref "X2") (pin "1") (pinfunction "KL_1") (pintype "passive"))
    )
    (net (code "61") (name "unconnected-(X2B-KL-Pad2)") (class "Default")
      (node (ref "X2") (pin "2") (pinfunction "KL_2") (pintype "passive"))
    )
    (net (code "62") (name "unconnected-(X3A-KL-Pad1)") (class "Default")
      (node (ref "X3") (pin "1") (pinfunction "KL_1") (pintype "passive"))
    )
    (net (code "63") (name "unconnected-(X3B-KL-Pad2)") (class "Default")
      (node (ref "X3") (pin "2") (pinfunction "KL_2") (pintype "passive"))
    )
    (net (code "64") (name "unconnected-(X4A-KL-Pad1)") (class "Default")
      (node (ref "X4") (pin "1") (pinfunction "KL_1") (pintype "passive"))
    )
    (net (code "65") (name "unconnected-(X5A-KL-Pad1)") (class "Default")
      (node (ref "X5") (pin "1") (pinfunction "KL_1") (pintype "passive"))
    )
    (net (code "66") (name "unconnected-(X6A-KL-Pad1)") (class "Default")
      (node (ref "X6") (pin "1") (pinfunction "KL_1") (pintype "passive"))
    )
    (net (code "67") (name "unconnected-(X7A-KL-Pad1)") (class "Default")
      (node (ref "X7") (pin "1") (pinfunction "KL_1") (pintype "passive"))
    )
    (net (code "68") (name "unconnected-(X9A-KL-Pad1)") (class "Default")
      (node (ref "X9") (pin "1") (pinfunction "KL_1") (pintype "passive"))
    )
    (net (code "69") (name "unconnected-(X10A-KL-Pad1)") (class "Default")
      (node (ref "X10") (pin "1") (pinfunction "KL_1") (pintype "passive"))
    )
    (net (code "70") (name "unconnected-(X11A-KL-Pad1)") (class "Default")
      (node (ref "X11") (pin "1") (pinfunction "KL_1") (pintype "passive"))
    )
    (net (code "71") (name "unconnected-(X12A-KL-Pad1)") (class "Default")
      (node (ref "X12") (pin "1") (pinfunction "KL_1") (pintype "passive"))
    )
    (net (code "72") (name "unconnected-(X14A-KL-Pad1)") (class "Default")
      (node (ref "X14") (pin "1") (pinfunction "KL_1") (pintype "passive"))
    )
    (net (code "73") (name "unconnected-(X14B-KL-Pad2)") (class "Default")
      (node (ref "X14") (pin "2") (pinfunction "KL_2") (pintype "passive"))
    )
    (net (code "74") (name "unconnected-(X15A-KL-Pad1)") (class "Default")
      (node (ref "X15") (pin "1") (pinfunction "KL_1") (pintype "passive"))
    )
    (net (code "75") (name "unconnected-(X15B-KL-Pad2)") (class "Default")
      (node (ref "X15") (pin "2") (pinfunction "KL_2") (pintype "passive"))
    )
    (net (code "76") (name "unconnected-(X16A-KL-Pad1)") (class "Default")
      (node (ref "X16") (pin "1") (pinfunction "KL_1") (pintype "passive"))
    )
    (net (code "77") (name "unconnected-(X16B-KL-Pad2)") (class "Default")
      (node (ref "X16") (pin "2") (pinfunction "KL_2") (pintype "passive"))
    )
  )
)
